# Motor_Driver.net
KiCad netlist of a schematic drawn in EAGLE
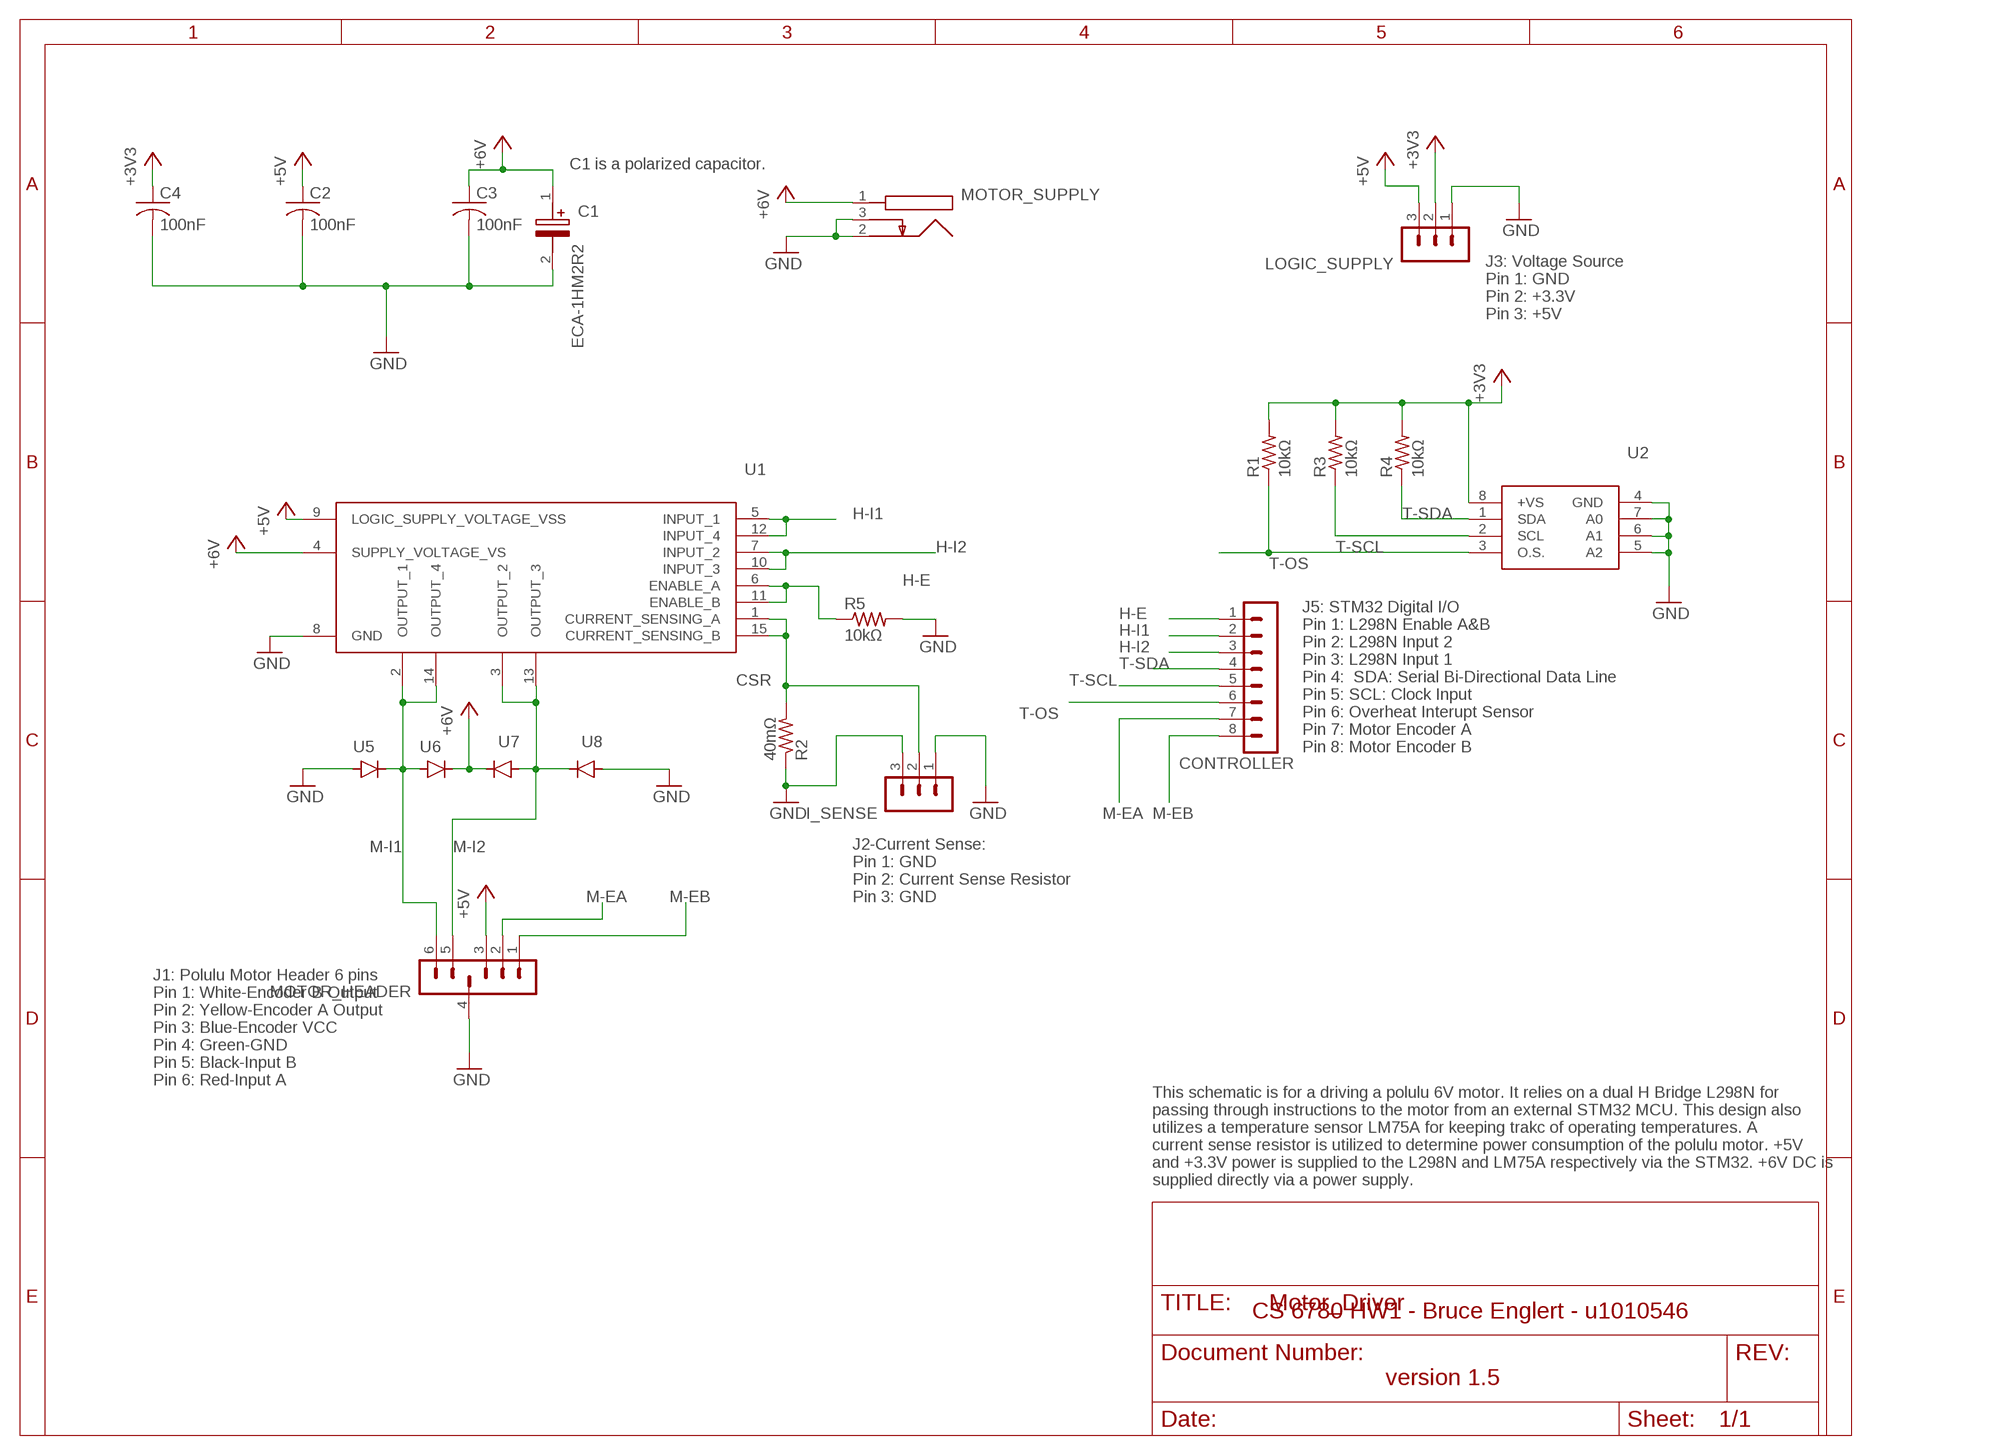
[diagram p0: schematic, sheet 1]

(export (version "E")
  (design (tool "Eeschema 10.0.6"))
  (components
    (comp (ref "C1")
      (value "ECA-1HM2R2")
      (footprint "eagle-import:CAPPRD200W55D500H1200")
      (fields (field (name "MOUSER_PART_NUMBER") "667-ECA-1HM2R2"))
      (libsource (lib "eagle-import") (part "ECA-1HM2R2"))
    )
    (comp (ref "C2")
      (value "100nF")
      (footprint "eagle-import:C1206")
      (libsource (lib "eagle-import") (part "C-USC1206"))
    )
    (comp (ref "C3")
      (value "100nF")
      (footprint "eagle-import:C1206")
      (libsource (lib "eagle-import") (part "C-USC1206"))
    )
    (comp (ref "C4")
      (value "100nF")
      (footprint "eagle-import:C1206")
      (libsource (lib "eagle-import") (part "C-USC1206"))
    )
    (comp (ref "CONTROLLER")
      (value "MA08-1")
      (footprint "eagle-import:MA08-1")
      (libsource (lib "eagle-import") (part "MA08-1"))
    )
    (comp (ref "I_SENSE")
      (value "CURRENT_SENSE")
      (footprint "eagle-import:MA03-1")
      (libsource (lib "eagle-import") (part "CURRENT_SENSE"))
    )
    (comp (ref "LOGIC_SUPPLY")
      (value "VOLTAGE_SOURCE")
      (footprint "eagle-import:MA03-1")
      (libsource (lib "eagle-import") (part "VOLTAGE_SOURCE"))
    )
    (comp (ref "MOTOR_HEADER")
      (value "MA06-1")
      (footprint "eagle-import:MA06-1")
      (libsource (lib "eagle-import") (part "MA06-1"))
    )
    (comp (ref "MOTOR_SUPPLY")
      (value "SUPPLY_JACK")
      (footprint "eagle-import:CONSOCJ2155")
      (fields
        (field (name "MANUFACTURER_PART_NUMBER") "CON-SOCJ-2155")
        (field (name "MOUSER_PART_NUMBER") "992-CON-SOCJ-2155")
      )
      (libsource (lib "eagle-import") (part "SUPPLY_JACK"))
    )
    (comp (ref "R1")
      (value "10kΩ")
      (footprint "eagle-import:R1206")
      (libsource (lib "eagle-import") (part "R-US_R1206"))
    )
    (comp (ref "R2")
      (value "40mΩ")
      (footprint "eagle-import:R1206")
      (libsource (lib "eagle-import") (part "R-US_R1206"))
    )
    (comp (ref "R3")
      (value "10kΩ")
      (footprint "eagle-import:R1206")
      (libsource (lib "eagle-import") (part "R-US_R1206"))
    )
    (comp (ref "R4")
      (value "10kΩ")
      (footprint "eagle-import:R1206")
      (libsource (lib "eagle-import") (part "R-US_R1206"))
    )
    (comp (ref "R5")
      (value "10kΩ")
      (footprint "eagle-import:R1206")
      (libsource (lib "eagle-import") (part "R-US_R1206"))
    )
    (comp (ref "U1")
      (value "L298N")
      (footprint "eagle-import:TO127P500X2020X2210-15P")
      (fields (field (name "MOUSER_PART_NUMBER") "511-L298"))
      (libsource (lib "eagle-import") (part "L298N"))
    )
    (comp (ref "U2")
      (value "LM75A")
      (footprint "eagle-import:SOIC127P600X175-8N")
      (fields
        (field (name "ARROW_PART_NUMBER") "LM75AIMX/NOPB")
        (field (name "MOUSER_PART_NUMBER") "926-LM75AIMX/NOPB")
      )
      (libsource (lib "eagle-import") (part "LM75A"))
    )
    (comp (ref "U5")
      (value "GF1")
      (footprint "eagle-import:SMA-DO214AC")
      (libsource (lib "eagle-import") (part "GF1"))
    )
    (comp (ref "U6")
      (value "GF1")
      (footprint "eagle-import:SMA-DO214AC")
      (libsource (lib "eagle-import") (part "GF1"))
    )
    (comp (ref "U7")
      (value "GF1")
      (footprint "eagle-import:SMA-DO214AC")
      (libsource (lib "eagle-import") (part "GF1"))
    )
    (comp (ref "U8")
      (value "GF1")
      (footprint "eagle-import:SMA-DO214AC")
      (libsource (lib "eagle-import") (part "GF1"))
    )
  )
  (nets
    (net (code "1") (name "+3V3") (class "Default")
      (node (ref "C4") (pin "1") (pinfunction "1_1") (pintype "passive"))
      (node (ref "LOGIC_SUPPLY") (pin "2") (pinfunction "2_2") (pintype "passive"))
      (node (ref "R1") (pin "2") (pinfunction "2_2") (pintype "passive"))
      (node (ref "R3") (pin "2") (pinfunction "2_2") (pintype "passive"))
      (node (ref "R4") (pin "2") (pinfunction "2_2") (pintype "passive"))
      (node (ref "U2") (pin "8") (pinfunction "+VS_8") (pintype "power_in"))
    )
    (net (code "2") (name "+5V") (class "Default")
      (node (ref "C2") (pin "1") (pinfunction "1_1") (pintype "passive"))
      (node (ref "LOGIC_SUPPLY") (pin "3") (pinfunction "3_3") (pintype "passive"))
      (node (ref "MOTOR_HEADER") (pin "3") (pinfunction "3_3") (pintype "passive"))
      (node (ref "U1") (pin "9") (pinfunction "LOGIC_SUPPLY_VOLTAGE_VSS_9") (pintype "power_in"))
    )
    (net (code "3") (name "+6V") (class "Default")
      (node (ref "C1") (pin "1") (pinfunction "+_1") (pintype "bidirectional"))
      (node (ref "C3") (pin "1") (pinfunction "1_1") (pintype "passive"))
      (node (ref "MOTOR_SUPPLY") (pin "1") (pinfunction "1_1") (pintype "bidirectional"))
      (node (ref "U1") (pin "4") (pinfunction "SUPPLY_VOLTAGE_VS_4") (pintype "power_in"))
      (node (ref "U6") (pin "K") (pinfunction "C_K") (pintype "passive"))
      (node (ref "U7") (pin "K") (pinfunction "C_K") (pintype "passive"))
    )
    (net (code "4") (name "/CSR") (class "Default")
      (node (ref "I_SENSE") (pin "2") (pinfunction "2_2") (pintype "passive"))
      (node (ref "R2") (pin "2") (pinfunction "2_2") (pintype "passive"))
      (node (ref "U1") (pin "1") (pinfunction "CURRENT_SENSING_A_1") (pintype "input"))
      (node (ref "U1") (pin "15") (pinfunction "CURRENT_SENSING_B_15") (pintype "input"))
    )
    (net (code "5") (name "/H-E") (class "Default")
      (node (ref "CONTROLLER") (pin "1") (pinfunction "1_1") (pintype "passive"))
      (node (ref "R5") (pin "1") (pinfunction "1_1") (pintype "passive"))
      (node (ref "U1") (pin "11") (pinfunction "ENABLE_B_11") (pintype "input"))
      (node (ref "U1") (pin "6") (pinfunction "ENABLE_A_6") (pintype "input"))
    )
    (net (code "6") (name "/H-I1") (class "Default")
      (node (ref "CONTROLLER") (pin "2") (pinfunction "2_2") (pintype "passive"))
      (node (ref "U1") (pin "12") (pinfunction "INPUT_4_12") (pintype "input"))
      (node (ref "U1") (pin "5") (pinfunction "INPUT_1_5") (pintype "input"))
    )
    (net (code "7") (name "/H-I2") (class "Default")
      (node (ref "CONTROLLER") (pin "3") (pinfunction "3_3") (pintype "passive"))
      (node (ref "U1") (pin "10") (pinfunction "INPUT_3_10") (pintype "input"))
      (node (ref "U1") (pin "7") (pinfunction "INPUT_2_7") (pintype "input"))
    )
    (net (code "8") (name "/M-EA") (class "Default")
      (node (ref "CONTROLLER") (pin "7") (pinfunction "7_7") (pintype "passive"))
      (node (ref "MOTOR_HEADER") (pin "2") (pinfunction "2_2") (pintype "passive"))
    )
    (net (code "9") (name "/M-EB") (class "Default")
      (node (ref "CONTROLLER") (pin "8") (pinfunction "8_8") (pintype "passive"))
      (node (ref "MOTOR_HEADER") (pin "1") (pinfunction "1_1") (pintype "passive"))
    )
    (net (code "10") (name "/M-I1") (class "Default")
      (node (ref "MOTOR_HEADER") (pin "6") (pinfunction "6_6") (pintype "passive"))
      (node (ref "U1") (pin "14") (pinfunction "OUTPUT_4_14") (pintype "output"))
      (node (ref "U1") (pin "2") (pinfunction "OUTPUT_1_2") (pintype "output"))
      (node (ref "U5") (pin "K") (pinfunction "C_K") (pintype "passive"))
      (node (ref "U6") (pin "A") (pinfunction "A_A") (pintype "passive"))
    )
    (net (code "11") (name "/M-I2") (class "Default")
      (node (ref "MOTOR_HEADER") (pin "5") (pinfunction "5_5") (pintype "passive"))
      (node (ref "U1") (pin "13") (pinfunction "OUTPUT_3_13") (pintype "output"))
      (node (ref "U1") (pin "3") (pinfunction "OUTPUT_2_3") (pintype "output"))
      (node (ref "U7") (pin "A") (pinfunction "A_A") (pintype "passive"))
      (node (ref "U8") (pin "K") (pinfunction "C_K") (pintype "passive"))
    )
    (net (code "12") (name "/T-OS") (class "Default")
      (node (ref "CONTROLLER") (pin "6") (pinfunction "6_6") (pintype "passive"))
      (node (ref "R1") (pin "1") (pinfunction "1_1") (pintype "passive"))
      (node (ref "U2") (pin "3") (pinfunction "O.S._3") (pintype "bidirectional"))
    )
    (net (code "13") (name "/T-SCL") (class "Default")
      (node (ref "CONTROLLER") (pin "5") (pinfunction "5_5") (pintype "passive"))
      (node (ref "R3") (pin "1") (pinfunction "1_1") (pintype "passive"))
      (node (ref "U2") (pin "2") (pinfunction "SCL_2") (pintype "bidirectional"))
    )
    (net (code "14") (name "/T-SDA") (class "Default")
      (node (ref "CONTROLLER") (pin "4") (pinfunction "4_4") (pintype "passive"))
      (node (ref "R4") (pin "1") (pinfunction "1_1") (pintype "passive"))
      (node (ref "U2") (pin "1") (pinfunction "SDA_1") (pintype "bidirectional"))
    )
    (net (code "15") (name "GND") (class "Default")
      (node (ref "C1") (pin "2") (pinfunction "-_2") (pintype "bidirectional"))
      (node (ref "C2") (pin "2") (pinfunction "2_2") (pintype "passive"))
      (node (ref "C3") (pin "2") (pinfunction "2_2") (pintype "passive"))
      (node (ref "C4") (pin "2") (pinfunction "2_2") (pintype "passive"))
      (node (ref "I_SENSE") (pin "1") (pinfunction "1_1") (pintype "passive"))
      (node (ref "I_SENSE") (pin "3") (pinfunction "3_3") (pintype "passive"))
      (node (ref "LOGIC_SUPPLY") (pin "1") (pinfunction "1_1") (pintype "passive"))
      (node (ref "MOTOR_HEADER") (pin "4") (pinfunction "4_4") (pintype "passive"))
      (node (ref "MOTOR_SUPPLY") (pin "2") (pinfunction "2_2") (pintype "bidirectional"))
      (node (ref "MOTOR_SUPPLY") (pin "3") (pinfunction "3_3") (pintype "bidirectional"))
      (node (ref "R2") (pin "1") (pinfunction "1_1") (pintype "passive"))
      (node (ref "R5") (pin "2") (pinfunction "2_2") (pintype "passive"))
      (node (ref "U1") (pin "8") (pinfunction "GND_8") (pintype "power_in"))
      (node (ref "U2") (pin "4") (pinfunction "GND_4") (pintype "power_in"))
      (node (ref "U2") (pin "5") (pinfunction "A2_5") (pintype "bidirectional"))
      (node (ref "U2") (pin "6") (pinfunction "A1_6") (pintype "bidirectional"))
      (node (ref "U2") (pin "7") (pinfunction "A0_7") (pintype "bidirectional"))
      (node (ref "U5") (pin "A") (pinfunction "A_A") (pintype "passive"))
      (node (ref "U8") (pin "A") (pinfunction "A_A") (pintype "passive"))
    )
  )
)
